# zmpt101b_-_3phase_din.net
KiCad netlist of a schematic drawn in EAGLE
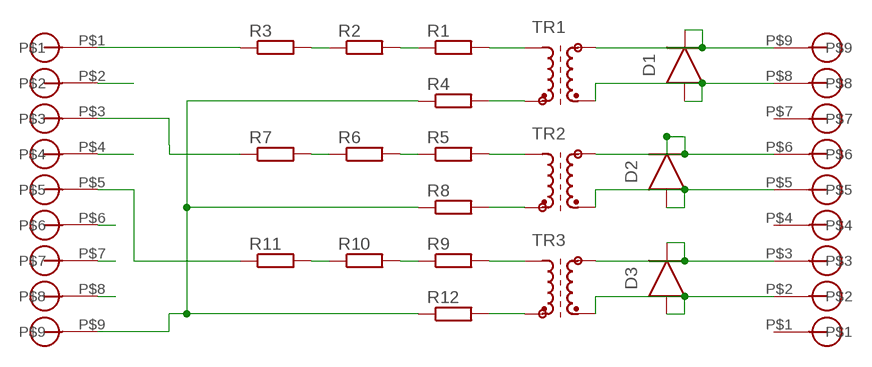
[diagram p0: schematic, sheet 1]

(export (version "E")
  (design (tool "Eeschema 10.0.6"))
  (components
    (comp (ref "D1")
      (value "DIODE_DO-219-AB(SOD123F)")
      (footprint "eagle-import:SODFL3718X115")
      (libsource (lib "eagle-import") (part "DIODEDO-219-AB(SOD123F)_"))
    )
    (comp (ref "D2")
      (value "DIODE_DO-219-AB(SOD123F)")
      (footprint "eagle-import:SODFL3718X115")
      (libsource (lib "eagle-import") (part "DIODEDO-219-AB(SOD123F)_"))
    )
    (comp (ref "D3")
      (value "DIODE_DO-219-AB(SOD123F)")
      (footprint "eagle-import:SODFL3718X115")
      (libsource (lib "eagle-import") (part "DIODEDO-219-AB(SOD123F)_"))
    )
    (comp (ref "R1")
      (value "R-EU_R1206")
      (footprint "eagle-import:R1206")
      (libsource (lib "eagle-import") (part "R-EU_R1206"))
    )
    (comp (ref "R2")
      (value "R-EU_R1206")
      (footprint "eagle-import:R1206")
      (libsource (lib "eagle-import") (part "R-EU_R1206"))
    )
    (comp (ref "R3")
      (value "R-EU_R1206")
      (footprint "eagle-import:R1206")
      (libsource (lib "eagle-import") (part "R-EU_R1206"))
    )
    (comp (ref "R4")
      (value "R-EU_R1206")
      (footprint "eagle-import:R1206")
      (libsource (lib "eagle-import") (part "R-EU_R1206"))
    )
    (comp (ref "R5")
      (value "R-EU_R1206")
      (footprint "eagle-import:R1206")
      (libsource (lib "eagle-import") (part "R-EU_R1206"))
    )
    (comp (ref "R6")
      (value "R-EU_R1206")
      (footprint "eagle-import:R1206")
      (libsource (lib "eagle-import") (part "R-EU_R1206"))
    )
    (comp (ref "R7")
      (value "R-EU_R1206")
      (footprint "eagle-import:R1206")
      (libsource (lib "eagle-import") (part "R-EU_R1206"))
    )
    (comp (ref "R8")
      (value "R-EU_R1206")
      (footprint "eagle-import:R1206")
      (libsource (lib "eagle-import") (part "R-EU_R1206"))
    )
    (comp (ref "R9")
      (value "R-EU_R1206")
      (footprint "eagle-import:R1206")
      (libsource (lib "eagle-import") (part "R-EU_R1206"))
    )
    (comp (ref "R10")
      (value "R-EU_R1206")
      (footprint "eagle-import:R1206")
      (libsource (lib "eagle-import") (part "R-EU_R1206"))
    )
    (comp (ref "R11")
      (value "R-EU_R1206")
      (footprint "eagle-import:R1206")
      (libsource (lib "eagle-import") (part "R-EU_R1206"))
    )
    (comp (ref "R12")
      (value "R-EU_R1206")
      (footprint "eagle-import:R1206")
      (libsource (lib "eagle-import") (part "R-EU_R1206"))
    )
    (comp (ref "TR1")
      (value "ZMPT101B")
      (footprint "eagle-import:ZMPT101B")
      (libsource (lib "eagle-import") (part "ZMPT101B"))
    )
    (comp (ref "TR2")
      (value "ZMPT101B")
      (footprint "eagle-import:ZMPT101B")
      (libsource (lib "eagle-import") (part "ZMPT101B"))
    )
    (comp (ref "TR3")
      (value "ZMPT101B")
      (footprint "eagle-import:ZMPT101B")
      (libsource (lib "eagle-import") (part "ZMPT101B"))
    )
    (comp (ref "U$1")
      (value "5MMBLOCK_X9")
      (footprint "eagle-import:9_5.08")
      (libsource (lib "eagle-import") (part "5MMBLOCK_X9"))
    )
    (comp (ref "U$2")
      (value "5MMBLOCK_X9")
      (footprint "eagle-import:9_5.08")
      (libsource (lib "eagle-import") (part "5MMBLOCK_X9"))
    )
  )
  (nets
    (net (code "1") (name "/P$1") (class "Default")
      (node (ref "U$2") (pin "P$1") (pinfunction "P$1_P$1") (pintype "power_in"))
    )
    (net (code "2") (name "/P$4") (class "Default")
      (node (ref "U$2") (pin "P$4") (pinfunction "P$4_P$4") (pintype "power_in"))
    )
    (net (code "3") (name "/P$7") (class "Default")
      (node (ref "U$2") (pin "P$7") (pinfunction "P$7_P$7") (pintype "power_in"))
    )
    (net (code "4") (name "Net-(D1-A)") (class "Default")
      (node (ref "D1") (pin "2") (pinfunction "A_2") (pintype "passive"))
      (node (ref "TR1") (pin "P$2") (pinfunction "E2_P$2") (pintype "passive"))
      (node (ref "U$2") (pin "P$8") (pinfunction "P$8_P$8") (pintype "power_in"))
    )
    (net (code "5") (name "Net-(D1-C)") (class "Default")
      (node (ref "D1") (pin "1") (pinfunction "C_1") (pintype "passive"))
      (node (ref "TR1") (pin "P$1") (pinfunction "A2_P$1") (pintype "passive"))
      (node (ref "U$2") (pin "P$9") (pinfunction "P$9_P$9") (pintype "power_in"))
    )
    (net (code "6") (name "Net-(D2-A)") (class "Default")
      (node (ref "D2") (pin "2") (pinfunction "A_2") (pintype "passive"))
      (node (ref "TR2") (pin "P$2") (pinfunction "E2_P$2") (pintype "passive"))
      (node (ref "U$2") (pin "P$5") (pinfunction "P$5_P$5") (pintype "power_in"))
    )
    (net (code "7") (name "Net-(D2-C)") (class "Default")
      (node (ref "D2") (pin "1") (pinfunction "C_1") (pintype "passive"))
      (node (ref "TR2") (pin "P$1") (pinfunction "A2_P$1") (pintype "passive"))
      (node (ref "U$2") (pin "P$6") (pinfunction "P$6_P$6") (pintype "power_in"))
    )
    (net (code "8") (name "Net-(D3-A)") (class "Default")
      (node (ref "D3") (pin "2") (pinfunction "A_2") (pintype "passive"))
      (node (ref "TR3") (pin "P$2") (pinfunction "E2_P$2") (pintype "passive"))
      (node (ref "U$2") (pin "P$2") (pinfunction "P$2_P$2") (pintype "power_in"))
    )
    (net (code "9") (name "Net-(D3-C)") (class "Default")
      (node (ref "D3") (pin "1") (pinfunction "C_1") (pintype "passive"))
      (node (ref "TR3") (pin "P$1") (pinfunction "A2_P$1") (pintype "passive"))
      (node (ref "U$2") (pin "P$3") (pinfunction "P$3_P$3") (pintype "power_in"))
    )
    (net (code "10") (name "Net-(R1-Pad1)") (class "Default")
      (node (ref "R1") (pin "1") (pinfunction "1_1") (pintype "passive"))
      (node (ref "R2") (pin "2") (pinfunction "2_2") (pintype "passive"))
    )
    (net (code "11") (name "Net-(R2-Pad1)") (class "Default")
      (node (ref "R2") (pin "1") (pinfunction "1_1") (pintype "passive"))
      (node (ref "R3") (pin "2") (pinfunction "2_2") (pintype "passive"))
    )
    (net (code "12") (name "Net-(R3-Pad1)") (class "Default")
      (node (ref "R3") (pin "1") (pinfunction "1_1") (pintype "passive"))
      (node (ref "U$1") (pin "P$1") (pinfunction "P$1_P$1") (pintype "power_in"))
    )
    (net (code "13") (name "Net-(R5-Pad1)") (class "Default")
      (node (ref "R5") (pin "1") (pinfunction "1_1") (pintype "passive"))
      (node (ref "R6") (pin "2") (pinfunction "2_2") (pintype "passive"))
    )
    (net (code "14") (name "Net-(R6-Pad1)") (class "Default")
      (node (ref "R6") (pin "1") (pinfunction "1_1") (pintype "passive"))
      (node (ref "R7") (pin "2") (pinfunction "2_2") (pintype "passive"))
    )
    (net (code "15") (name "Net-(R7-Pad1)") (class "Default")
      (node (ref "R7") (pin "1") (pinfunction "1_1") (pintype "passive"))
      (node (ref "U$1") (pin "P$3") (pinfunction "P$3_P$3") (pintype "power_in"))
    )
    (net (code "16") (name "Net-(R10-Pad1)") (class "Default")
      (node (ref "R10") (pin "1") (pinfunction "1_1") (pintype "passive"))
      (node (ref "R11") (pin "2") (pinfunction "2_2") (pintype "passive"))
    )
    (net (code "17") (name "Net-(R10-Pad2)") (class "Default")
      (node (ref "R10") (pin "2") (pinfunction "2_2") (pintype "passive"))
      (node (ref "R9") (pin "1") (pinfunction "1_1") (pintype "passive"))
    )
    (net (code "18") (name "Net-(R11-Pad1)") (class "Default")
      (node (ref "R11") (pin "1") (pinfunction "1_1") (pintype "passive"))
      (node (ref "U$1") (pin "P$5") (pinfunction "P$5_P$5") (pintype "power_in"))
    )
    (net (code "19") (name "Net-(R12-Pad1)") (class "Default")
      (node (ref "R12") (pin "1") (pinfunction "1_1") (pintype "passive"))
      (node (ref "R4") (pin "1") (pinfunction "1_1") (pintype "passive"))
      (node (ref "R8") (pin "1") (pinfunction "1_1") (pintype "passive"))
      (node (ref "U$1") (pin "P$9") (pinfunction "P$9_P$9") (pintype "power_in"))
    )
    (net (code "20") (name "Net-(TR1-A1)") (class "Default")
      (node (ref "R1") (pin "2") (pinfunction "2_2") (pintype "passive"))
      (node (ref "TR1") (pin "P$4") (pinfunction "A1_P$4") (pintype "passive"))
    )
    (net (code "21") (name "Net-(TR1-E1)") (class "Default")
      (node (ref "R4") (pin "2") (pinfunction "2_2") (pintype "passive"))
      (node (ref "TR1") (pin "P$3") (pinfunction "E1_P$3") (pintype "passive"))
    )
    (net (code "22") (name "Net-(TR2-A1)") (class "Default")
      (node (ref "R5") (pin "2") (pinfunction "2_2") (pintype "passive"))
      (node (ref "TR2") (pin "P$4") (pinfunction "A1_P$4") (pintype "passive"))
    )
    (net (code "23") (name "Net-(TR2-E1)") (class "Default")
      (node (ref "R8") (pin "2") (pinfunction "2_2") (pintype "passive"))
      (node (ref "TR2") (pin "P$3") (pinfunction "E1_P$3") (pintype "passive"))
    )
    (net (code "24") (name "Net-(TR3-A1)") (class "Default")
      (node (ref "R9") (pin "2") (pinfunction "2_2") (pintype "passive"))
      (node (ref "TR3") (pin "P$4") (pinfunction "A1_P$4") (pintype "passive"))
    )
    (net (code "25") (name "Net-(TR3-E1)") (class "Default")
      (node (ref "R12") (pin "2") (pinfunction "2_2") (pintype "passive"))
      (node (ref "TR3") (pin "P$3") (pinfunction "E1_P$3") (pintype "passive"))
    )
    (net (code "26") (name "unconnected-(U$1-PadP$2)") (class "Default")
      (node (ref "U$1") (pin "P$2") (pinfunction "P$2_P$2") (pintype "power_in"))
    )
    (net (code "27") (name "unconnected-(U$1-PadP$4)") (class "Default")
      (node (ref "U$1") (pin "P$4") (pinfunction "P$4_P$4") (pintype "power_in"))
    )
    (net (code "28") (name "unconnected-(U$1-PadP$6)") (class "Default")
      (node (ref "U$1") (pin "P$6") (pinfunction "P$6_P$6") (pintype "power_in"))
    )
    (net (code "29") (name "unconnected-(U$1-PadP$7)") (class "Default")
      (node (ref "U$1") (pin "P$7") (pinfunction "P$7_P$7") (pintype "power_in"))
    )
    (net (code "30") (name "unconnected-(U$1-PadP$8)") (class "Default")
      (node (ref "U$1") (pin "P$8") (pinfunction "P$8_P$8") (pintype "power_in"))
    )
  )
)
